# PWR_SEPIC_P12V_N12V.net
KiCad netlist of a schematic drawn in Altium Designer
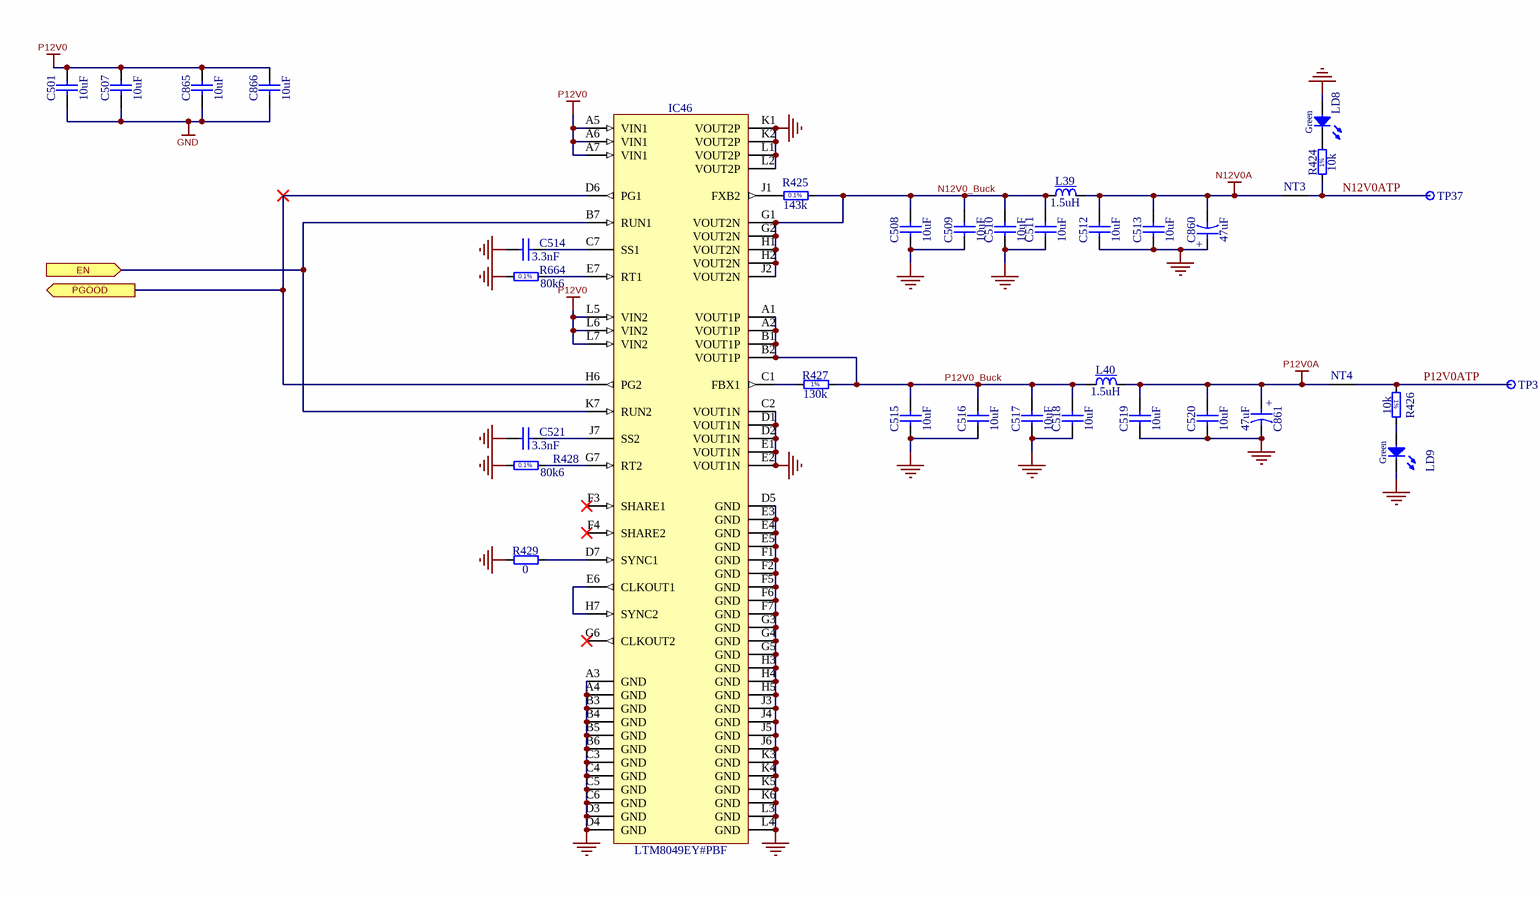
[diagram p0: PWR_SEPIC_P12V_N12V.SchDoc]

(export (version "E")
  (design (tool "Eeschema 10.0.6"))
  (components
    (comp (ref "C501")
      (value "10uF")
      (footprint "CAPC2012X95N")
      (description "Non-polarised capacitor")
      (fields
        (field (name "MANUFACTURER PART NUMBER") "CC0805_10UF_25V_10%_X5R")
        (field (name "MANUFACTURER") "GENERIC")
        (field (name "AUTHOR") "CERN DEM JLC")
      )
      (libsource (lib "Capacitors") (part "Capacitor - non polarized"))
    )
    (comp (ref "C507")
      (value "10uF")
      (footprint "CAPC2012X95N")
      (description "Non-polarised capacitor")
      (fields
        (field (name "MANUFACTURER PART NUMBER") "CC0805_10UF_25V_10%_X5R")
        (field (name "MANUFACTURER") "GENERIC")
        (field (name "AUTHOR") "CERN DEM JLC")
      )
      (libsource (lib "Capacitors") (part "Capacitor - non polarized"))
    )
    (comp (ref "C508")
      (value "10uF")
      (footprint "CAPC2012X95N")
      (description "Non-polarised capacitor")
      (fields
        (field (name "MANUFACTURER PART NUMBER") "CC0805_10UF_25V_10%_X5R")
        (field (name "MANUFACTURER") "GENERIC")
        (field (name "AUTHOR") "CERN DEM JLC")
      )
      (libsource (lib "Capacitors") (part "Capacitor - non polarized"))
    )
    (comp (ref "C509")
      (value "10uF")
      (footprint "CAPC2012X95N")
      (description "Non-polarised capacitor")
      (fields
        (field (name "MANUFACTURER PART NUMBER") "CC0805_10UF_25V_10%_X5R")
        (field (name "MANUFACTURER") "GENERIC")
        (field (name "AUTHOR") "CERN DEM JLC")
      )
      (libsource (lib "Capacitors") (part "Capacitor - non polarized"))
    )
    (comp (ref "C510")
      (value "10uF")
      (footprint "CAPC2012X95N")
      (description "Non-polarised capacitor")
      (fields
        (field (name "MANUFACTURER PART NUMBER") "CC0805_10UF_25V_10%_X5R")
        (field (name "MANUFACTURER") "GENERIC")
        (field (name "AUTHOR") "CERN DEM JLC")
      )
      (libsource (lib "Capacitors") (part "Capacitor - non polarized"))
    )
    (comp (ref "C511")
      (value "10uF")
      (footprint "CAPC2012X95N")
      (description "Non-polarised capacitor")
      (fields
        (field (name "MANUFACTURER PART NUMBER") "CC0805_10UF_25V_10%_X5R")
        (field (name "MANUFACTURER") "GENERIC")
        (field (name "AUTHOR") "CERN DEM JLC")
      )
      (libsource (lib "Capacitors") (part "Capacitor - non polarized"))
    )
    (comp (ref "C512")
      (value "10uF")
      (footprint "CAPC2012X95N")
      (description "Non-polarised capacitor")
      (fields
        (field (name "MANUFACTURER PART NUMBER") "CC0805_10UF_25V_10%_X5R")
        (field (name "MANUFACTURER") "GENERIC")
        (field (name "AUTHOR") "CERN DEM JLC")
      )
      (libsource (lib "Capacitors") (part "Capacitor - non polarized"))
    )
    (comp (ref "C513")
      (value "10uF")
      (footprint "CAPC2012X95N")
      (description "Non-polarised capacitor")
      (fields
        (field (name "MANUFACTURER PART NUMBER") "CC0805_10UF_25V_10%_X5R")
        (field (name "MANUFACTURER") "GENERIC")
        (field (name "AUTHOR") "CERN DEM JLC")
      )
      (libsource (lib "Capacitors") (part "Capacitor - non polarized"))
    )
    (comp (ref "C514")
      (value "3.3nF")
      (footprint "CAPC1005X55N")
      (description "Non-polarised capacitor")
      (fields
        (field (name "MANUFACTURER PART NUMBER") "CC0402_3.3NF_50V_10%_X7R")
        (field (name "MANUFACTURER") "GENERIC")
        (field (name "AUTHOR") "CERN DEM JLC")
      )
      (libsource (lib "Capacitors") (part "Capacitor - non polarized"))
    )
    (comp (ref "C515")
      (value "10uF")
      (footprint "CAPC2012X95N")
      (description "Non-polarised capacitor")
      (fields
        (field (name "MANUFACTURER PART NUMBER") "CC0805_10UF_25V_10%_X5R")
        (field (name "MANUFACTURER") "GENERIC")
        (field (name "AUTHOR") "CERN DEM JLC")
      )
      (libsource (lib "Capacitors") (part "Capacitor - non polarized"))
    )
    (comp (ref "C516")
      (value "10uF")
      (footprint "CAPC2012X95N")
      (description "Non-polarised capacitor")
      (fields
        (field (name "MANUFACTURER PART NUMBER") "CC0805_10UF_25V_10%_X5R")
        (field (name "MANUFACTURER") "GENERIC")
        (field (name "AUTHOR") "CERN DEM JLC")
      )
      (libsource (lib "Capacitors") (part "Capacitor - non polarized"))
    )
    (comp (ref "C517")
      (value "10uF")
      (footprint "CAPC2012X95N")
      (description "Non-polarised capacitor")
      (fields
        (field (name "MANUFACTURER PART NUMBER") "CC0805_10UF_25V_10%_X5R")
        (field (name "MANUFACTURER") "GENERIC")
        (field (name "AUTHOR") "CERN DEM JLC")
      )
      (libsource (lib "Capacitors") (part "Capacitor - non polarized"))
    )
    (comp (ref "C518")
      (value "10uF")
      (footprint "CAPC2012X95N")
      (description "Non-polarised capacitor")
      (fields
        (field (name "MANUFACTURER PART NUMBER") "CC0805_10UF_25V_10%_X5R")
        (field (name "MANUFACTURER") "GENERIC")
        (field (name "AUTHOR") "CERN DEM JLC")
      )
      (libsource (lib "Capacitors") (part "Capacitor - non polarized"))
    )
    (comp (ref "C519")
      (value "10uF")
      (footprint "CAPC2012X95N")
      (description "Non-polarised capacitor")
      (fields
        (field (name "MANUFACTURER PART NUMBER") "CC0805_10UF_25V_10%_X5R")
        (field (name "MANUFACTURER") "GENERIC")
        (field (name "AUTHOR") "CERN DEM JLC")
      )
      (libsource (lib "Capacitors") (part "Capacitor - non polarized"))
    )
    (comp (ref "C520")
      (value "10uF")
      (footprint "CAPC2012X95N")
      (description "Non-polarised capacitor")
      (fields
        (field (name "MANUFACTURER PART NUMBER") "CC0805_10UF_25V_10%_X5R")
        (field (name "MANUFACTURER") "GENERIC")
        (field (name "AUTHOR") "CERN DEM JLC")
      )
      (libsource (lib "Capacitors") (part "Capacitor - non polarized"))
    )
    (comp (ref "C521")
      (value "3.3nF")
      (footprint "CAPC1005X55N")
      (description "Non-polarised capacitor")
      (fields
        (field (name "MANUFACTURER PART NUMBER") "CC0402_3.3NF_50V_10%_X7R")
        (field (name "MANUFACTURER") "GENERIC")
        (field (name "AUTHOR") "CERN DEM JLC")
      )
      (libsource (lib "Capacitors") (part "Capacitor - non polarized"))
    )
    (comp (ref "C860")
      (value "47uF")
      (footprint "CAPMP6032X280N")
      (description "Polarised capacitor")
      (fields
        (field (name "MANUFACTURER PART NUMBER") "CTE6032-28_47UF_16V_10%_LESR0350")
        (field (name "MANUFACTURER") "GENERIC")
        (field (name "AUTHOR") "CERN DEM JLC")
      )
      (libsource (lib "Capacitors") (part "Capacitor - polarized"))
    )
    (comp (ref "C861")
      (value "47uF")
      (footprint "CAPMP6032X280N")
      (description "Polarised capacitor")
      (fields
        (field (name "MANUFACTURER PART NUMBER") "CTE6032-28_47UF_16V_10%_LESR0350")
        (field (name "MANUFACTURER") "GENERIC")
        (field (name "AUTHOR") "CERN DEM JLC")
      )
      (libsource (lib "Capacitors") (part "Capacitor - polarized"))
    )
    (comp (ref "C865")
      (value "10uF")
      (footprint "CAPC2012X95N")
      (description "Non-polarised capacitor")
      (fields
        (field (name "MANUFACTURER PART NUMBER") "CC0805_10UF_25V_10%_X5R")
        (field (name "MANUFACTURER") "GENERIC")
        (field (name "AUTHOR") "CERN DEM JLC")
      )
      (libsource (lib "Capacitors") (part "Capacitor - non polarized"))
    )
    (comp (ref "C866")
      (value "10uF")
      (footprint "CAPC2012X95N")
      (description "Non-polarised capacitor")
      (fields
        (field (name "MANUFACTURER PART NUMBER") "CC0805_10UF_25V_10%_X5R")
        (field (name "MANUFACTURER") "GENERIC")
        (field (name "AUTHOR") "CERN DEM JLC")
      )
      (libsource (lib "Capacitors") (part "Capacitor - non polarized"))
    )
    (comp (ref "IC46")
      (value "LTM8049EY#PBF")
      (footprint "BGA77C127P7X11_900X1500X262")
      (description "Dual SEPIC or Inverting uModule DC/DC Converter")
      (fields (field (name "MANUFACTURER") "LINEAR TECHNOLOGY") (field (name "AUTHOR") "CERN DEM JLC"))
      (libsource (lib "ICs And Semiconductors") (part "LTM8049"))
    )
    (comp (ref "L39")
      (value "1.5uH")
      (footprint "IND_TDK_SPM6530")
      (description "Inductor With Core")
      (fields
        (field (name "MANUFACTURER PART NUMBER") "SPM6530T-1R5M100")
        (field (name "MANUFACTURER") "TDK")
        (field (name "AUTHOR") "CERN DEM MR")
      )
      (libsource (lib "Inductors & Transformers") (part "Inductor With Magnetic core"))
    )
    (comp (ref "L40")
      (value "1.5uH")
      (footprint "IND_TDK_SPM6530")
      (description "Inductor With Core")
      (fields
        (field (name "MANUFACTURER PART NUMBER") "SPM6530T-1R5M100")
        (field (name "MANUFACTURER") "TDK")
        (field (name "AUTHOR") "CERN DEM MR")
      )
      (libsource (lib "Inductors & Transformers") (part "Inductor With Magnetic core"))
    )
    (comp (ref "LD8")
      (value "Green")
      (footprint "LED_KINGBRIGHT_KPH-1608CGCK")
      (description "LED Green 1C 2A")
      (fields
        (field (name "PART NUMBER") "LED_KINGBRIGHT_KPH-1608CGCK")
        (field (name "MANUFACTURER") "KINGBRIGHT")
        (field (name "AUTHOR") "CERN DEM JLC")
      )
      (libsource (lib "ICs And Semiconductors") (part "LED Green 1C 2A"))
    )
    (comp (ref "LD9")
      (value "Green")
      (footprint "LED_KINGBRIGHT_KPH-1608CGCK")
      (description "LED Green 1C 2A")
      (fields
        (field (name "PART NUMBER") "LED_KINGBRIGHT_KPH-1608CGCK")
        (field (name "MANUFACTURER") "KINGBRIGHT")
        (field (name "AUTHOR") "CERN DEM JLC")
      )
      (libsource (lib "ICs And Semiconductors") (part "LED Green 1C 2A"))
    )
    (comp (ref "NT3")
      (value "Net Tie")
      (footprint "Net Tie")
      (fields (field (name "AUTHOR") "CERN DEM JLC"))
      (libsource (lib "Eletro-mechanical") (part "Net Tie"))
    )
    (comp (ref "NT4")
      (value "Net Tie")
      (footprint "Net Tie")
      (fields (field (name "AUTHOR") "CERN DEM JLC"))
      (libsource (lib "Eletro-mechanical") (part "Net Tie"))
    )
    (comp (ref "R424")
      (value "10k")
      (footprint "RESC1005X40N")
      (description "Resistor - 1%")
      (fields
        (field (name "MANUFACTURER PART NUMBER") "R0402_10K_1%_0.0625W_100PPM")
        (field (name "MANUFACTURER") "GENERIC")
        (field (name "AUTHOR") "CERN DEM JLC")
      )
      (libsource (lib "Resistors") (part "Resistor - 1%"))
    )
    (comp (ref "R425")
      (value "143k")
      (footprint "RESC1608X55N")
      (description "Resistor - 0.1%")
      (fields
        (field (name "MANUFACTURER PART NUMBER") "R0603_143K_0.1%_0.063W_10PPM")
        (field (name "MANUFACTURER") "GENERIC")
        (field (name "AUTHOR") "CERN DEM JLC")
      )
      (libsource (lib "Resistors") (part "Resistor - 0.1%"))
    )
    (comp (ref "R426")
      (value "10k")
      (footprint "RESC1005X40N")
      (description "Resistor - 1%")
      (fields
        (field (name "MANUFACTURER PART NUMBER") "R0402_10K_1%_0.0625W_100PPM")
        (field (name "MANUFACTURER") "GENERIC")
        (field (name "AUTHOR") "CERN DEM JLC")
      )
      (libsource (lib "Resistors") (part "Resistor - 1%"))
    )
    (comp (ref "R427")
      (value "130k")
      (footprint "RESC1005X40N")
      (description "Resistor - 1%")
      (fields
        (field (name "MANUFACTURER PART NUMBER") "R0402_130K_1%_0.0625W_100PPM")
        (field (name "MANUFACTURER") "GENERIC")
        (field (name "AUTHOR") "CERN DEM JLC")
      )
      (libsource (lib "Resistors") (part "Resistor - 1%"))
    )
    (comp (ref "R428")
      (value "80k6")
      (footprint "RESC1608X55N")
      (description "Resistor - 0.1%")
      (fields
        (field (name "MANUFACTURER PART NUMBER") "R0603_80K6_0.1%_0.063W_10PPM")
        (field (name "MANUFACTURER") "GENERIC")
        (field (name "AUTHOR") "CERN DEM JLC")
      )
      (libsource (lib "Resistors") (part "Resistor - 0.1%"))
    )
    (comp (ref "R429")
      (value "0")
      (footprint "RESC1005X40N")
      (description "Resistor")
      (fields
        (field (name "MANUFACTURER PART NUMBER") "R0402_0R_JUMPER")
        (field (name "MANUFACTURER") "GENERIC")
        (field (name "AUTHOR") "CERN DEM JLC")
      )
      (libsource (lib "Resistors") (part "Resistor"))
    )
    (comp (ref "R664")
      (value "80k6")
      (footprint "RESC1608X55N")
      (description "Resistor - 0.1%")
      (fields
        (field (name "MANUFACTURER PART NUMBER") "R0603_80K6_0.1%_0.063W_10PPM")
        (field (name "MANUFACTURER") "GENERIC")
        (field (name "AUTHOR") "CERN DEM JLC")
      )
      (libsource (lib "Resistors") (part "Resistor - 0.1%"))
    )
    (comp (ref "TP37")
      (value "Test Point")
      (footprint "TPS127")
      (fields (field (name "PART NUMBER") "SMD_PAD_1.27X1.27MM") (field (name "AUTHOR") "CERN DEM JLC"))
      (libsource (lib "Eletro-mechanical") (part "Test Point"))
    )
    (comp (ref "TP38")
      (value "Test Point")
      (footprint "TPS127")
      (fields (field (name "PART NUMBER") "SMD_PAD_1.27X1.27MM") (field (name "AUTHOR") "CERN DEM JLC"))
      (libsource (lib "Eletro-mechanical") (part "Test Point"))
    )
  )
  (nets
    (net (code "1") (name "/EN") (class "Default")
      (node (ref "IC46") (pin "B7") (pinfunction "RUN1_B7") (pintype "input"))
      (node (ref "IC46") (pin "K7") (pinfunction "RUN2_K7") (pintype "input"))
    )
    (net (code "2") (name "/N12V0ATP") (class "Default")
      (node (ref "NT3") (pin "2") (pinfunction "2_2") (pintype "bidirectional"))
      (node (ref "R424") (pin "1") (pinfunction "1_1") (pintype "passive"))
      (node (ref "TP37") (pin "1") (pinfunction "1_1") (pintype "bidirectional"))
    )
    (net (code "3") (name "/N12V0_Buck") (class "Default")
      (node (ref "C508") (pin "2") (pinfunction "2_2") (pintype "passive"))
      (node (ref "C509") (pin "2") (pinfunction "2_2") (pintype "passive"))
      (node (ref "C510") (pin "2") (pinfunction "2_2") (pintype "passive"))
      (node (ref "C511") (pin "2") (pinfunction "2_2") (pintype "passive"))
      (node (ref "IC46") (pin "G1") (pinfunction "VOUT2N_G1") (pintype "power_in"))
      (node (ref "IC46") (pin "G2") (pinfunction "VOUT2N_G2") (pintype "power_in"))
      (node (ref "IC46") (pin "H1") (pinfunction "VOUT2N_H1") (pintype "power_in"))
      (node (ref "IC46") (pin "H2") (pinfunction "VOUT2N_H2") (pintype "power_in"))
      (node (ref "IC46") (pin "J2") (pinfunction "VOUT2N_J2") (pintype "power_in"))
      (node (ref "L39") (pin "1") (pinfunction "1_1") (pintype "passive"))
      (node (ref "R425") (pin "2") (pinfunction "2_2") (pintype "passive"))
    )
    (net (code "4") (name "/P12V0ATP") (class "Default")
      (node (ref "NT4") (pin "2") (pinfunction "2_2") (pintype "bidirectional"))
      (node (ref "R426") (pin "1") (pinfunction "1_1") (pintype "passive"))
      (node (ref "TP38") (pin "1") (pinfunction "1_1") (pintype "bidirectional"))
    )
    (net (code "5") (name "/P12V0_Buck") (class "Default")
      (node (ref "C515") (pin "2") (pinfunction "2_2") (pintype "passive"))
      (node (ref "C516") (pin "2") (pinfunction "2_2") (pintype "passive"))
      (node (ref "C517") (pin "2") (pinfunction "2_2") (pintype "passive"))
      (node (ref "C518") (pin "2") (pinfunction "2_2") (pintype "passive"))
      (node (ref "IC46") (pin "A1") (pinfunction "VOUT1P_A1") (pintype "power_in"))
      (node (ref "IC46") (pin "A2") (pinfunction "VOUT1P_A2") (pintype "power_in"))
      (node (ref "IC46") (pin "B1") (pinfunction "VOUT1P_B1") (pintype "power_in"))
      (node (ref "IC46") (pin "B2") (pinfunction "VOUT1P_B2") (pintype "power_in"))
      (node (ref "L40") (pin "1") (pinfunction "1_1") (pintype "passive"))
      (node (ref "R427") (pin "2") (pinfunction "2_2") (pintype "passive"))
    )
    (net (code "6") (name "/PGOOD") (class "Default")
      (node (ref "IC46") (pin "D6") (pinfunction "PG1_D6") (pintype "output"))
      (node (ref "IC46") (pin "H6") (pinfunction "PG2_H6") (pintype "output"))
    )
    (net (code "7") (name "GND") (class "Default")
      (node (ref "C501") (pin "1") (pinfunction "1_1") (pintype "passive"))
      (node (ref "C507") (pin "1") (pinfunction "1_1") (pintype "passive"))
      (node (ref "C508") (pin "1") (pinfunction "1_1") (pintype "passive"))
      (node (ref "C509") (pin "1") (pinfunction "1_1") (pintype "passive"))
      (node (ref "C510") (pin "1") (pinfunction "1_1") (pintype "passive"))
      (node (ref "C511") (pin "1") (pinfunction "1_1") (pintype "passive"))
      (node (ref "C512") (pin "1") (pinfunction "1_1") (pintype "passive"))
      (node (ref "C513") (pin "1") (pinfunction "1_1") (pintype "passive"))
      (node (ref "C514") (pin "1") (pinfunction "1_1") (pintype "passive"))
      (node (ref "C515") (pin "1") (pinfunction "1_1") (pintype "passive"))
      (node (ref "C516") (pin "1") (pinfunction "1_1") (pintype "passive"))
      (node (ref "C517") (pin "1") (pinfunction "1_1") (pintype "passive"))
      (node (ref "C518") (pin "1") (pinfunction "1_1") (pintype "passive"))
      (node (ref "C519") (pin "1") (pinfunction "1_1") (pintype "passive"))
      (node (ref "C520") (pin "1") (pinfunction "1_1") (pintype "passive"))
      (node (ref "C521") (pin "1") (pinfunction "1_1") (pintype "passive"))
      (node (ref "C860") (pin "1") (pinfunction "1_1") (pintype "passive"))
      (node (ref "C861") (pin "2") (pinfunction "2_2") (pintype "passive"))
      (node (ref "C865") (pin "1") (pinfunction "1_1") (pintype "passive"))
      (node (ref "C866") (pin "1") (pinfunction "1_1") (pintype "passive"))
      (node (ref "IC46") (pin "A3") (pinfunction "GND_A3") (pintype "power_in"))
      (node (ref "IC46") (pin "A4") (pinfunction "GND_A4") (pintype "power_in"))
      (node (ref "IC46") (pin "B3") (pinfunction "GND_B3") (pintype "power_in"))
      (node (ref "IC46") (pin "B4") (pinfunction "GND_B4") (pintype "power_in"))
      (node (ref "IC46") (pin "B5") (pinfunction "GND_B5") (pintype "power_in"))
      (node (ref "IC46") (pin "B6") (pinfunction "GND_B6") (pintype "power_in"))
      (node (ref "IC46") (pin "C2") (pinfunction "VOUT1N_C2") (pintype "power_in"))
      (node (ref "IC46") (pin "C3") (pinfunction "GND_C3") (pintype "power_in"))
      (node (ref "IC46") (pin "C4") (pinfunction "GND_C4") (pintype "power_in"))
      (node (ref "IC46") (pin "C5") (pinfunction "GND_C5") (pintype "power_in"))
      (node (ref "IC46") (pin "C6") (pinfunction "GND_C6") (pintype "power_in"))
      (node (ref "IC46") (pin "D1") (pinfunction "VOUT1N_D1") (pintype "power_in"))
      (node (ref "IC46") (pin "D2") (pinfunction "VOUT1N_D2") (pintype "power_in"))
      (node (ref "IC46") (pin "D3") (pinfunction "GND_D3") (pintype "power_in"))
      (node (ref "IC46") (pin "D4") (pinfunction "GND_D4") (pintype "power_in"))
      (node (ref "IC46") (pin "D5") (pinfunction "GND_D5") (pintype "power_in"))
      (node (ref "IC46") (pin "E1") (pinfunction "VOUT1N_E1") (pintype "power_in"))
      (node (ref "IC46") (pin "E2") (pinfunction "VOUT1N_E2") (pintype "power_in"))
      (node (ref "IC46") (pin "E3") (pinfunction "GND_E3") (pintype "power_in"))
      (node (ref "IC46") (pin "E4") (pinfunction "GND_E4") (pintype "power_in"))
      (node (ref "IC46") (pin "E5") (pinfunction "GND_E5") (pintype "power_in"))
      (node (ref "IC46") (pin "F1") (pinfunction "GND_F1") (pintype "power_in"))
      (node (ref "IC46") (pin "F2") (pinfunction "GND_F2") (pintype "power_in"))
      (node (ref "IC46") (pin "F5") (pinfunction "GND_F5") (pintype "power_in"))
      (node (ref "IC46") (pin "F6") (pinfunction "GND_F6") (pintype "power_in"))
      (node (ref "IC46") (pin "F7") (pinfunction "GND_F7") (pintype "power_in"))
      (node (ref "IC46") (pin "G3") (pinfunction "GND_G3") (pintype "power_in"))
      (node (ref "IC46") (pin "G4") (pinfunction "GND_G4") (pintype "power_in"))
      (node (ref "IC46") (pin "G5") (pinfunction "GND_G5") (pintype "power_in"))
      (node (ref "IC46") (pin "H3") (pinfunction "GND_H3") (pintype "power_in"))
      (node (ref "IC46") (pin "H4") (pinfunction "GND_H4") (pintype "power_in"))
      (node (ref "IC46") (pin "H5") (pinfunction "GND_H5") (pintype "power_in"))
      (node (ref "IC46") (pin "J3") (pinfunction "GND_J3") (pintype "power_in"))
      (node (ref "IC46") (pin "J4") (pinfunction "GND_J4") (pintype "power_in"))
      (node (ref "IC46") (pin "J5") (pinfunction "GND_J5") (pintype "power_in"))
      (node (ref "IC46") (pin "J6") (pinfunction "GND_J6") (pintype "power_in"))
      (node (ref "IC46") (pin "K1") (pinfunction "VOUT2P_K1") (pintype "power_in"))
      (node (ref "IC46") (pin "K2") (pinfunction "VOUT2P_K2") (pintype "power_in"))
      (node (ref "IC46") (pin "K3") (pinfunction "GND_K3") (pintype "power_in"))
      (node (ref "IC46") (pin "K4") (pinfunction "GND_K4") (pintype "power_in"))
      (node (ref "IC46") (pin "K5") (pinfunction "GND_K5") (pintype "power_in"))
      (node (ref "IC46") (pin "K6") (pinfunction "GND_K6") (pintype "power_in"))
      (node (ref "IC46") (pin "L1") (pinfunction "VOUT2P_L1") (pintype "power_in"))
      (node (ref "IC46") (pin "L2") (pinfunction "VOUT2P_L2") (pintype "power_in"))
      (node (ref "IC46") (pin "L3") (pinfunction "GND_L3") (pintype "power_in"))
      (node (ref "IC46") (pin "L4") (pinfunction "GND_L4") (pintype "power_in"))
      (node (ref "LD8") (pin "2") (pinfunction "A_2") (pintype "passive"))
      (node (ref "LD9") (pin "1") (pinfunction "C_1") (pintype "passive"))
      (node (ref "R428") (pin "1") (pinfunction "1_1") (pintype "passive"))
      (node (ref "R429") (pin "1") (pinfunction "1_1") (pintype "passive"))
      (node (ref "R664") (pin "1") (pinfunction "1_1") (pintype "passive"))
    )
    (net (code "8") (name "N12V0A") (class "Default")
      (node (ref "C512") (pin "2") (pinfunction "2_2") (pintype "passive"))
      (node (ref "C513") (pin "2") (pinfunction "2_2") (pintype "passive"))
      (node (ref "C860") (pin "2") (pinfunction "2_2") (pintype "passive"))
      (node (ref "L39") (pin "2") (pinfunction "2_2") (pintype "passive"))
      (node (ref "NT3") (pin "1") (pinfunction "1_1") (pintype "bidirectional"))
    )
    (net (code "9") (name "Net-(IC46-CLKOUT1)") (class "Default")
      (node (ref "IC46") (pin "E6") (pinfunction "CLKOUT1_E6") (pintype "output"))
      (node (ref "IC46") (pin "H7") (pinfunction "SYNC2_H7") (pintype "input"))
    )
    (net (code "10") (name "Net-(IC46-FBX1)") (class "Default")
      (node (ref "IC46") (pin "C1") (pinfunction "FBX1_C1") (pintype "output"))
      (node (ref "R427") (pin "1") (pinfunction "1_1") (pintype "passive"))
    )
    (net (code "11") (name "Net-(IC46-FXB2)") (class "Default")
      (node (ref "IC46") (pin "J1") (pinfunction "FXB2_J1") (pintype "output"))
      (node (ref "R425") (pin "1") (pinfunction "1_1") (pintype "passive"))
    )
    (net (code "12") (name "Net-(IC46-RT1)") (class "Default")
      (node (ref "IC46") (pin "E7") (pinfunction "RT1_E7") (pintype "input"))
      (node (ref "R664") (pin "2") (pinfunction "2_2") (pintype "passive"))
    )
    (net (code "13") (name "Net-(IC46-RT2)") (class "Default")
      (node (ref "IC46") (pin "G7") (pinfunction "RT2_G7") (pintype "input"))
      (node (ref "R428") (pin "2") (pinfunction "2_2") (pintype "passive"))
    )
    (net (code "14") (name "Net-(IC46-SS1)") (class "Default")
      (node (ref "C514") (pin "2") (pinfunction "2_2") (pintype "passive"))
      (node (ref "IC46") (pin "C7") (pinfunction "SS1_C7") (pintype "passive"))
    )
    (net (code "15") (name "Net-(IC46-SS2)") (class "Default")
      (node (ref "C521") (pin "2") (pinfunction "2_2") (pintype "passive"))
      (node (ref "IC46") (pin "J7") (pinfunction "SS2_J7") (pintype "passive"))
    )
    (net (code "16") (name "Net-(IC46-SYNC1)") (class "Default")
      (node (ref "IC46") (pin "D7") (pinfunction "SYNC1_D7") (pintype "input"))
      (node (ref "R429") (pin "2") (pinfunction "2_2") (pintype "passive"))
    )
    (net (code "17") (name "Net-(LD8-C)") (class "Default")
      (node (ref "LD8") (pin "1") (pinfunction "C_1") (pintype "passive"))
      (node (ref "R424") (pin "2") (pinfunction "2_2") (pintype "passive"))
    )
    (net (code "18") (name "Net-(LD9-A)") (class "Default")
      (node (ref "LD9") (pin "2") (pinfunction "A_2") (pintype "passive"))
      (node (ref "R426") (pin "2") (pinfunction "2_2") (pintype "passive"))
    )
    (net (code "19") (name "P12V0") (class "Default")
      (node (ref "C501") (pin "2") (pinfunction "2_2") (pintype "passive"))
      (node (ref "C507") (pin "2") (pinfunction "2_2") (pintype "passive"))
      (node (ref "C865") (pin "2") (pinfunction "2_2") (pintype "passive"))
      (node (ref "C866") (pin "2") (pinfunction "2_2") (pintype "passive"))
      (node (ref "IC46") (pin "A5") (pinfunction "VIN1_A5") (pintype "input"))
      (node (ref "IC46") (pin "A6") (pinfunction "VIN1_A6") (pintype "input"))
      (node (ref "IC46") (pin "A7") (pinfunction "VIN1_A7") (pintype "input"))
      (node (ref "IC46") (pin "L5") (pinfunction "VIN2_L5") (pintype "input"))
      (node (ref "IC46") (pin "L6") (pinfunction "VIN2_L6") (pintype "input"))
      (node (ref "IC46") (pin "L7") (pinfunction "VIN2_L7") (pintype "input"))
    )
    (net (code "20") (name "P12V0A") (class "Default")
      (node (ref "C519") (pin "2") (pinfunction "2_2") (pintype "passive"))
      (node (ref "C520") (pin "2") (pinfunction "2_2") (pintype "passive"))
      (node (ref "C861") (pin "1") (pinfunction "1_1") (pintype "passive"))
      (node (ref "L40") (pin "2") (pinfunction "2_2") (pintype "passive"))
      (node (ref "NT4") (pin "1") (pinfunction "1_1") (pintype "bidirectional"))
    )
    (net (code "21") (name "unconnected-(IC46-CLKOUT2-PadG6)") (class "Default")
      (node (ref "IC46") (pin "G6") (pinfunction "CLKOUT2_G6") (pintype "output+no_connect"))
    )
    (net (code "22") (name "unconnected-(IC46-SHARE1-PadF3)") (class "Default")
      (node (ref "IC46") (pin "F3") (pinfunction "SHARE1_F3") (pintype "input+no_connect"))
    )
    (net (code "23") (name "unconnected-(IC46-SHARE2-PadF4)") (class "Default")
      (node (ref "IC46") (pin "F4") (pinfunction "SHARE2_F4") (pintype "input+no_connect"))
    )
  )
)
